# shiftreg-io.net
KiCad netlist of a schematic drawn in EAGLE
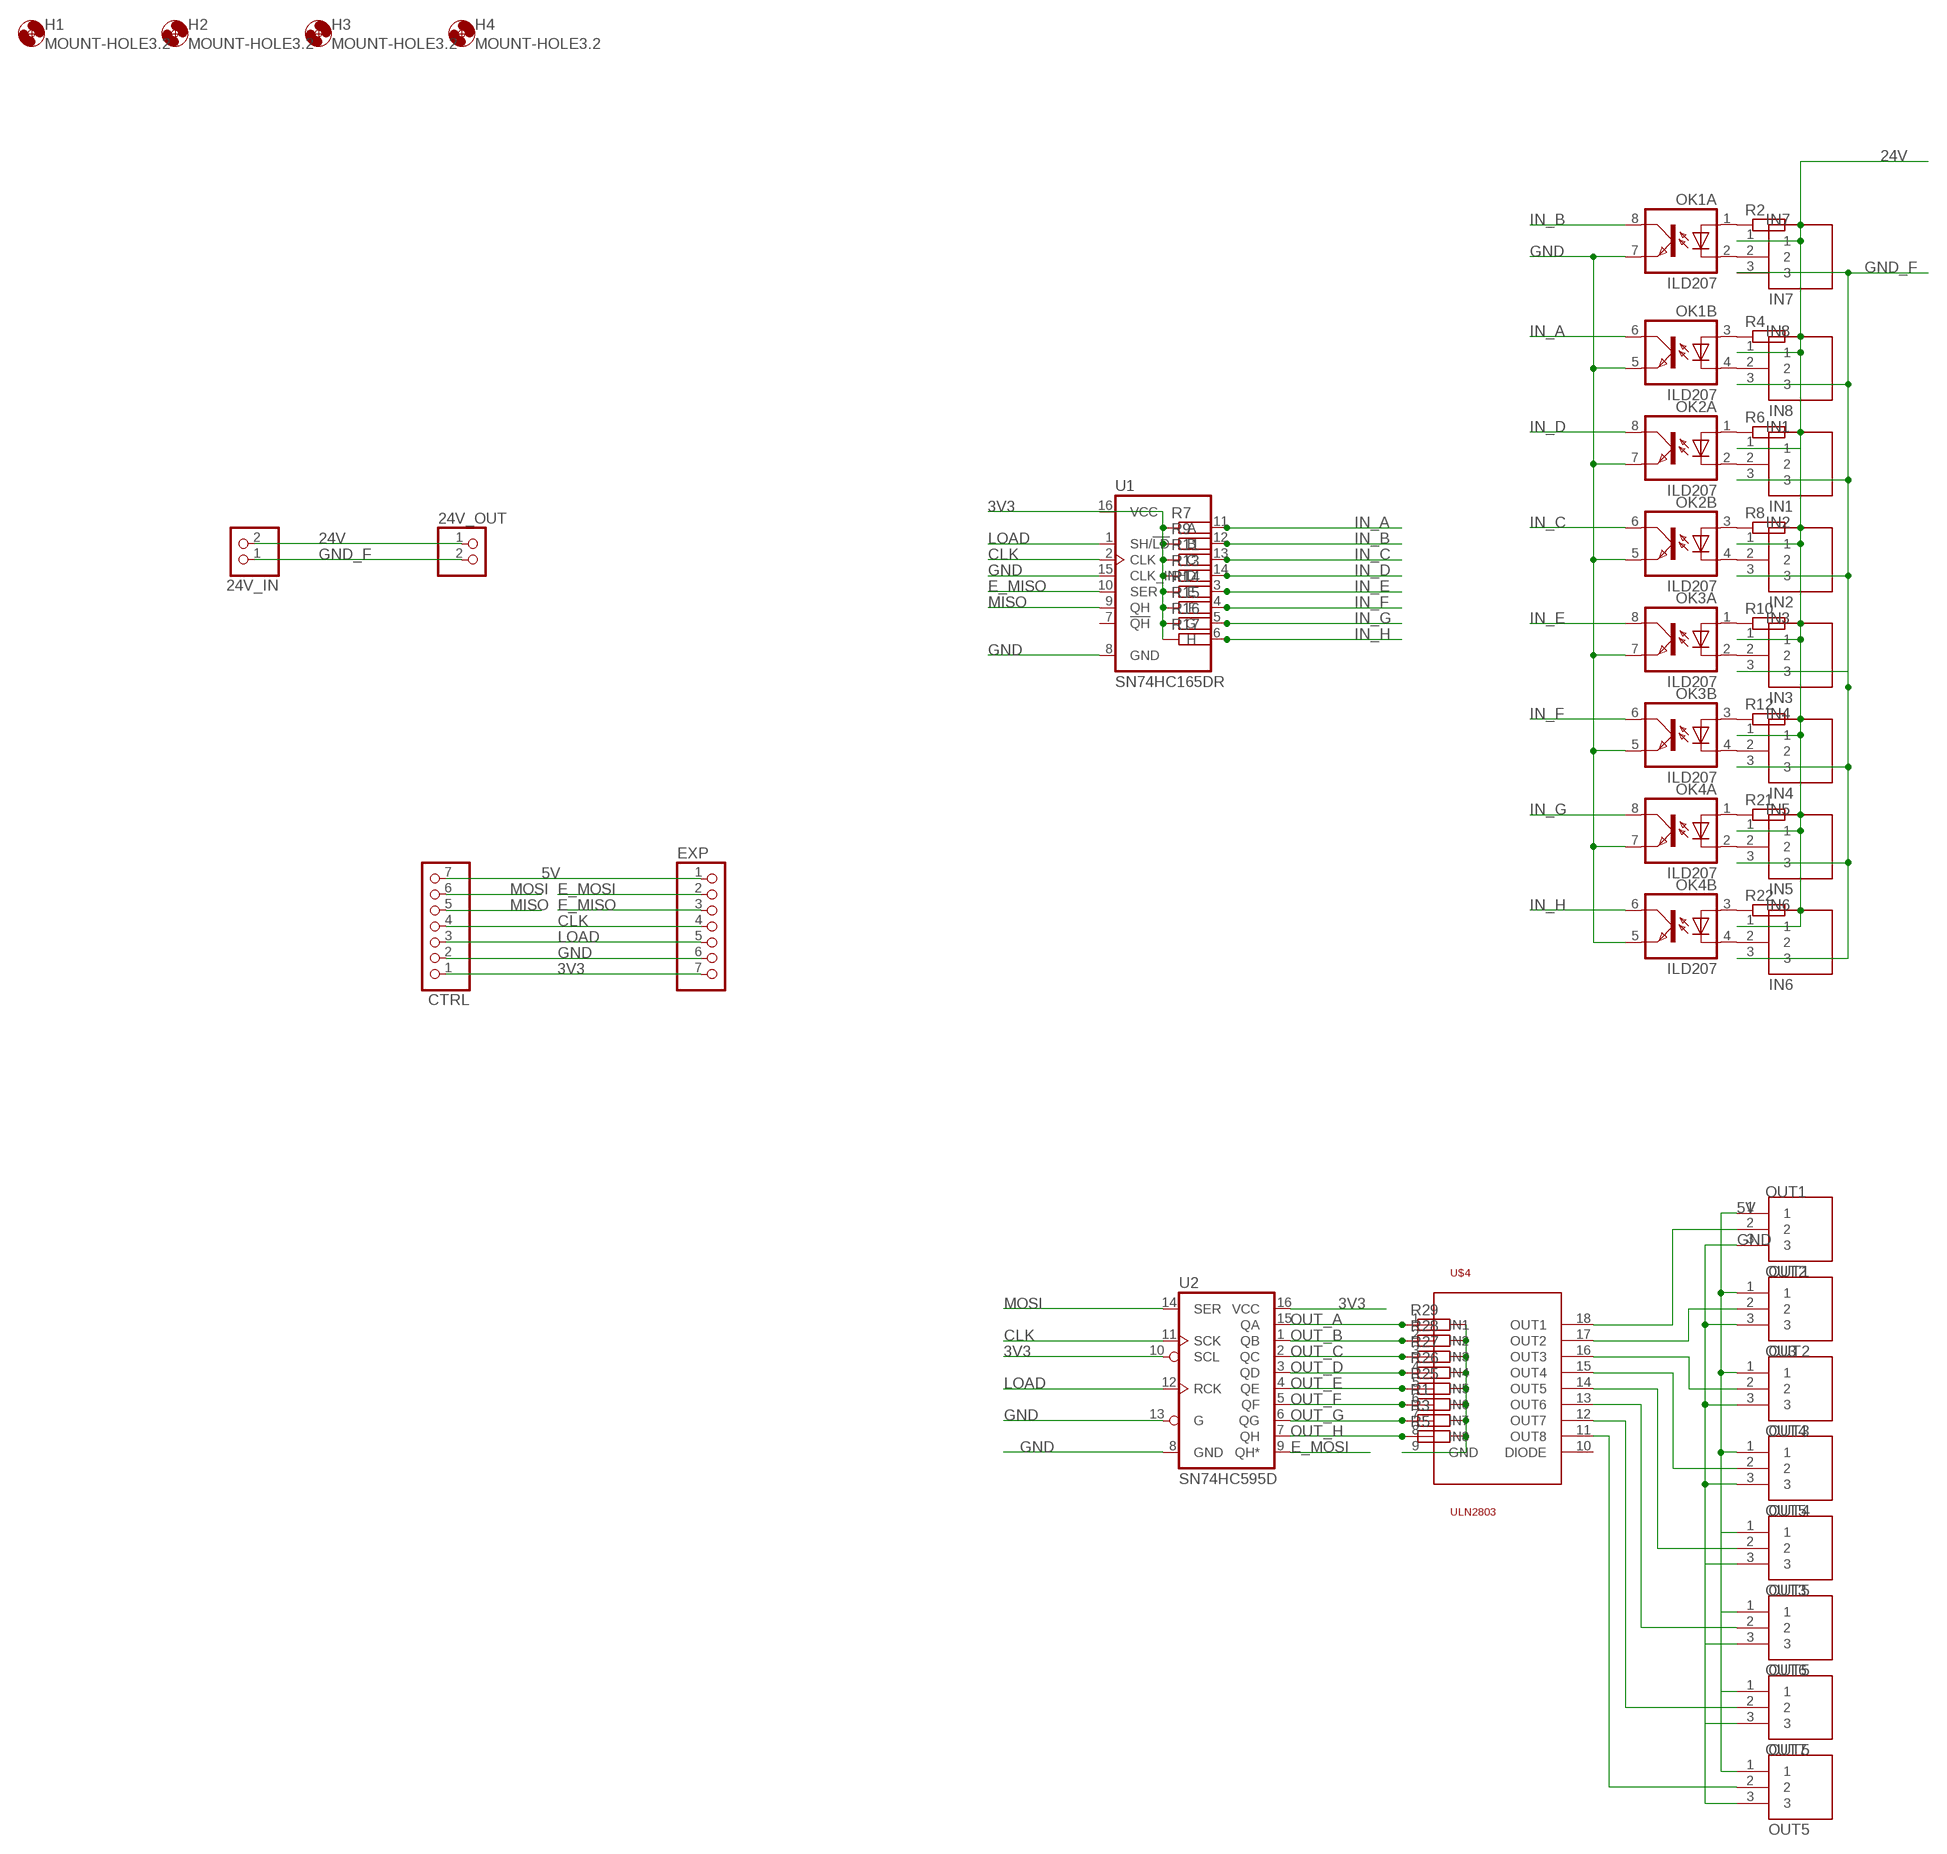
[diagram p0: schematic, sheet 1]

(export (version "E")
  (design (tool "Eeschema 10.0.6"))
  (components
    (comp (ref "24V_IN")
      (value "PINHD-1X2")
      (footprint "eagle-import:1X02")
      (libsource (lib "eagle-import") (part "PINHD-1X2"))
    )
    (comp (ref "24V_OUT")
      (value "PINHD-1X2")
      (footprint "eagle-import:1X02")
      (libsource (lib "eagle-import") (part "PINHD-1X2"))
    )
    (comp (ref "CTRL")
      (value "PINHD-1X7")
      (footprint "eagle-import:1X07")
      (libsource (lib "eagle-import") (part "PINHD-1X7"))
    )
    (comp (ref "EXP")
      (value "PINHD-1X7")
      (footprint "eagle-import:1X07")
      (libsource (lib "eagle-import") (part "PINHD-1X7"))
    )
    (comp (ref "H1")
      (value "MOUNT-HOLE3.2")
      (footprint "eagle-import:3,2")
      (libsource (lib "eagle-import") (part "MOUNT-HOLE3.2"))
    )
    (comp (ref "H2")
      (value "MOUNT-HOLE3.2")
      (footprint "eagle-import:3,2")
      (libsource (lib "eagle-import") (part "MOUNT-HOLE3.2"))
    )
    (comp (ref "H3")
      (value "MOUNT-HOLE3.2")
      (footprint "eagle-import:3,2")
      (libsource (lib "eagle-import") (part "MOUNT-HOLE3.2"))
    )
    (comp (ref "H4")
      (value "MOUNT-HOLE3.2")
      (footprint "eagle-import:3,2")
      (libsource (lib "eagle-import") (part "MOUNT-HOLE3.2"))
    )
    (comp (ref "IN1")
      (value "IN1")
      (footprint "eagle-import:TE_284512-3")
      (fields (field (name "COMMENT") "284512-3") (field (name "MF") "TE Connectivity"))
      (libsource (lib "eagle-import") (part "284512-3"))
    )
    (comp (ref "IN2")
      (value "IN2")
      (footprint "eagle-import:TE_284512-3")
      (fields (field (name "COMMENT") "284512-3") (field (name "MF") "TE Connectivity"))
      (libsource (lib "eagle-import") (part "284512-3"))
    )
    (comp (ref "IN3")
      (value "IN3")
      (footprint "eagle-import:TE_284512-3")
      (fields (field (name "COMMENT") "284512-3") (field (name "MF") "TE Connectivity"))
      (libsource (lib "eagle-import") (part "284512-3"))
    )
    (comp (ref "IN4")
      (value "IN4")
      (footprint "eagle-import:TE_284512-3")
      (fields (field (name "COMMENT") "284512-3") (field (name "MF") "TE Connectivity"))
      (libsource (lib "eagle-import") (part "284512-3"))
    )
    (comp (ref "IN5")
      (value "IN5")
      (footprint "eagle-import:TE_284512-3")
      (fields (field (name "COMMENT") "284512-3") (field (name "MF") "TE Connectivity"))
      (libsource (lib "eagle-import") (part "284512-3"))
    )
    (comp (ref "IN6")
      (value "IN6")
      (footprint "eagle-import:TE_284512-3")
      (fields (field (name "COMMENT") "284512-3") (field (name "MF") "TE Connectivity"))
      (libsource (lib "eagle-import") (part "284512-3"))
    )
    (comp (ref "IN7")
      (value "IN7")
      (footprint "eagle-import:TE_284512-3")
      (fields (field (name "COMMENT") "284512-3") (field (name "MF") "TE Connectivity"))
      (libsource (lib "eagle-import") (part "284512-3"))
    )
    (comp (ref "IN8")
      (value "IN8")
      (footprint "eagle-import:TE_284512-3")
      (fields (field (name "COMMENT") "284512-3") (field (name "MF") "TE Connectivity"))
      (libsource (lib "eagle-import") (part "284512-3"))
    )
    (comp (ref "OK1")
      (value "ILD207")
      (footprint "eagle-import:SOIC08")
      (fields (field (name "MF") "VISHAY/TELEFUNKEN") (field (name "MPN") "ILD207T"))
      (libsource (lib "eagle-import") (part "ILD207"))
    )
    (comp (ref "OK2")
      (value "ILD207")
      (footprint "eagle-import:SOIC08")
      (fields (field (name "MF") "VISHAY/TELEFUNKEN") (field (name "MPN") "ILD207T"))
      (libsource (lib "eagle-import") (part "ILD207"))
    )
    (comp (ref "OK3")
      (value "ILD207")
      (footprint "eagle-import:SOIC08")
      (fields (field (name "MF") "VISHAY/TELEFUNKEN") (field (name "MPN") "ILD207T"))
      (libsource (lib "eagle-import") (part "ILD207"))
    )
    (comp (ref "OK4")
      (value "ILD207")
      (footprint "eagle-import:SOIC08")
      (fields (field (name "MF") "VISHAY/TELEFUNKEN") (field (name "MPN") "ILD207T"))
      (libsource (lib "eagle-import") (part "ILD207"))
    )
    (comp (ref "OU3")
      (value "OUT3")
      (footprint "eagle-import:TE_284512-3")
      (fields (field (name "COMMENT") "284512-3") (field (name "MF") "TE Connectivity"))
      (libsource (lib "eagle-import") (part "284512-3"))
    )
    (comp (ref "OUT1")
      (value "OUT1")
      (footprint "eagle-import:TE_284512-3")
      (fields (field (name "COMMENT") "284512-3") (field (name "MF") "TE Connectivity"))
      (libsource (lib "eagle-import") (part "284512-3"))
    )
    (comp (ref "OUT2")
      (value "OUT2")
      (footprint "eagle-import:TE_284512-3")
      (fields (field (name "COMMENT") "284512-3") (field (name "MF") "TE Connectivity"))
      (libsource (lib "eagle-import") (part "284512-3"))
    )
    (comp (ref "OUT3")
      (value "OUT5")
      (footprint "eagle-import:TE_284512-3")
      (fields (field (name "COMMENT") "284512-3") (field (name "MF") "TE Connectivity"))
      (libsource (lib "eagle-import") (part "284512-3"))
    )
    (comp (ref "OUT4")
      (value "OUT4")
      (footprint "eagle-import:TE_284512-3")
      (fields (field (name "COMMENT") "284512-3") (field (name "MF") "TE Connectivity"))
      (libsource (lib "eagle-import") (part "284512-3"))
    )
    (comp (ref "OUT5")
      (value "OUT5")
      (footprint "eagle-import:TE_284512-3")
      (fields (field (name "COMMENT") "284512-3") (field (name "MF") "TE Connectivity"))
      (libsource (lib "eagle-import") (part "284512-3"))
    )
    (comp (ref "OUT6")
      (value "OUT5")
      (footprint "eagle-import:TE_284512-3")
      (fields (field (name "COMMENT") "284512-3") (field (name "MF") "TE Connectivity"))
      (libsource (lib "eagle-import") (part "284512-3"))
    )
    (comp (ref "OUT7")
      (value "OUT5")
      (footprint "eagle-import:TE_284512-3")
      (fields (field (name "COMMENT") "284512-3") (field (name "MF") "TE Connectivity"))
      (libsource (lib "eagle-import") (part "284512-3"))
    )
    (comp (ref "R1")
      (value "R-EU_M0805")
      (footprint "eagle-import:M0805")
      (libsource (lib "eagle-import") (part "R-EU_M0805"))
    )
    (comp (ref "R2")
      (value "R-EU_M0805")
      (footprint "eagle-import:M0805")
      (libsource (lib "eagle-import") (part "R-EU_M0805"))
    )
    (comp (ref "R3")
      (value "R-EU_M0805")
      (footprint "eagle-import:M0805")
      (libsource (lib "eagle-import") (part "R-EU_M0805"))
    )
    (comp (ref "R4")
      (value "R-EU_M0805")
      (footprint "eagle-import:M0805")
      (libsource (lib "eagle-import") (part "R-EU_M0805"))
    )
    (comp (ref "R5")
      (value "R-EU_M0805")
      (footprint "eagle-import:M0805")
      (libsource (lib "eagle-import") (part "R-EU_M0805"))
    )
    (comp (ref "R6")
      (value "R-EU_M0805")
      (footprint "eagle-import:M0805")
      (libsource (lib "eagle-import") (part "R-EU_M0805"))
    )
    (comp (ref "R7")
      (value "R-EU_M0805")
      (footprint "eagle-import:M0805")
      (libsource (lib "eagle-import") (part "R-EU_M0805"))
    )
    (comp (ref "R8")
      (value "R-EU_M0805")
      (footprint "eagle-import:M0805")
      (libsource (lib "eagle-import") (part "R-EU_M0805"))
    )
    (comp (ref "R9")
      (value "R-EU_M0805")
      (footprint "eagle-import:M0805")
      (libsource (lib "eagle-import") (part "R-EU_M0805"))
    )
    (comp (ref "R10")
      (value "R-EU_M0805")
      (footprint "eagle-import:M0805")
      (libsource (lib "eagle-import") (part "R-EU_M0805"))
    )
    (comp (ref "R11")
      (value "R-EU_M0805")
      (footprint "eagle-import:M0805")
      (libsource (lib "eagle-import") (part "R-EU_M0805"))
    )
    (comp (ref "R12")
      (value "R-EU_M0805")
      (footprint "eagle-import:M0805")
      (libsource (lib "eagle-import") (part "R-EU_M0805"))
    )
    (comp (ref "R13")
      (value "R-EU_M0805")
      (footprint "eagle-import:M0805")
      (libsource (lib "eagle-import") (part "R-EU_M0805"))
    )
    (comp (ref "R14")
      (value "R-EU_M0805")
      (footprint "eagle-import:M0805")
      (libsource (lib "eagle-import") (part "R-EU_M0805"))
    )
    (comp (ref "R15")
      (value "R-EU_M0805")
      (footprint "eagle-import:M0805")
      (libsource (lib "eagle-import") (part "R-EU_M0805"))
    )
    (comp (ref "R16")
      (value "R-EU_M0805")
      (footprint "eagle-import:M0805")
      (libsource (lib "eagle-import") (part "R-EU_M0805"))
    )
    (comp (ref "R17")
      (value "R-EU_M0805")
      (footprint "eagle-import:M0805")
      (libsource (lib "eagle-import") (part "R-EU_M0805"))
    )
    (comp (ref "R21")
      (value "R-EU_M0805")
      (footprint "eagle-import:M0805")
      (libsource (lib "eagle-import") (part "R-EU_M0805"))
    )
    (comp (ref "R22")
      (value "R-EU_M0805")
      (footprint "eagle-import:M0805")
      (libsource (lib "eagle-import") (part "R-EU_M0805"))
    )
    (comp (ref "R25")
      (value "R-EU_M0805")
      (footprint "eagle-import:M0805")
      (libsource (lib "eagle-import") (part "R-EU_M0805"))
    )
    (comp (ref "R26")
      (value "R-EU_M0805")
      (footprint "eagle-import:M0805")
      (libsource (lib "eagle-import") (part "R-EU_M0805"))
    )
    (comp (ref "R27")
      (value "R-EU_M0805")
      (footprint "eagle-import:M0805")
      (libsource (lib "eagle-import") (part "R-EU_M0805"))
    )
    (comp (ref "R28")
      (value "R-EU_M0805")
      (footprint "eagle-import:M0805")
      (libsource (lib "eagle-import") (part "R-EU_M0805"))
    )
    (comp (ref "R29")
      (value "R-EU_M0805")
      (footprint "eagle-import:M0805")
      (libsource (lib "eagle-import") (part "R-EU_M0805"))
    )
    (comp (ref "U$4")
      (value "ULN2803")
      (footprint "eagle-import:SO18L")
      (libsource (lib "eagle-import") (part "ULN2803"))
    )
    (comp (ref "U1")
      (value "SN74HC165DR")
      (footprint "eagle-import:SO16")
      (libsource (lib "eagle-import") (part "74165DHC"))
    )
    (comp (ref "U2")
      (value "SN74HC595D")
      (footprint "eagle-import:SO16")
      (libsource (lib "eagle-import") (part "74595DHC"))
    )
  )
  (nets
    (net (code "1") (name "/3V3") (class "Default")
      (node (ref "CTRL") (pin "1") (pinfunction "1_1") (pintype "passive"))
      (node (ref "EXP") (pin "7") (pinfunction "7_7") (pintype "passive"))
      (node (ref "R11") (pin "1") (pinfunction "1_1") (pintype "passive"))
      (node (ref "R13") (pin "1") (pinfunction "1_1") (pintype "passive"))
      (node (ref "R14") (pin "1") (pinfunction "1_1") (pintype "passive"))
      (node (ref "R15") (pin "1") (pinfunction "1_1") (pintype "passive"))
      (node (ref "R16") (pin "1") (pinfunction "1_1") (pintype "passive"))
      (node (ref "R17") (pin "1") (pinfunction "1_1") (pintype "passive"))
      (node (ref "R7") (pin "1") (pinfunction "1_1") (pintype "passive"))
      (node (ref "R9") (pin "1") (pinfunction "1_1") (pintype "passive"))
      (node (ref "U1") (pin "16") (pinfunction "VCC_16") (pintype "power_in"))
      (node (ref "U2") (pin "10") (pinfunction "SCL_10") (pintype "input"))
      (node (ref "U2") (pin "16") (pinfunction "VCC_16") (pintype "power_in"))
    )
    (net (code "2") (name "/5V") (class "Default")
      (node (ref "CTRL") (pin "7") (pinfunction "7_7") (pintype "passive"))
      (node (ref "EXP") (pin "1") (pinfunction "1_1") (pintype "passive"))
      (node (ref "OU3") (pin "1") (pinfunction "1_1") (pintype "passive"))
      (node (ref "OUT1") (pin "1") (pinfunction "1_1") (pintype "passive"))
      (node (ref "OUT2") (pin "1") (pinfunction "1_1") (pintype "passive"))
      (node (ref "OUT3") (pin "1") (pinfunction "1_1") (pintype "passive"))
      (node (ref "OUT4") (pin "1") (pinfunction "1_1") (pintype "passive"))
      (node (ref "OUT5") (pin "1") (pinfunction "1_1") (pintype "passive"))
      (node (ref "OUT6") (pin "1") (pinfunction "1_1") (pintype "passive"))
      (node (ref "OUT7") (pin "1") (pinfunction "1_1") (pintype "passive"))
    )
    (net (code "3") (name "/24V") (class "Default")
      (node (ref "24V_IN") (pin "2") (pinfunction "2_2") (pintype "passive"))
      (node (ref "24V_OUT") (pin "1") (pinfunction "1_1") (pintype "passive"))
      (node (ref "IN1") (pin "1") (pinfunction "1_1") (pintype "passive"))
      (node (ref "IN2") (pin "1") (pinfunction "1_1") (pintype "passive"))
      (node (ref "IN3") (pin "1") (pinfunction "1_1") (pintype "passive"))
      (node (ref "IN4") (pin "1") (pinfunction "1_1") (pintype "passive"))
      (node (ref "IN5") (pin "1") (pinfunction "1_1") (pintype "passive"))
      (node (ref "IN6") (pin "1") (pinfunction "1_1") (pintype "passive"))
      (node (ref "IN7") (pin "1") (pinfunction "1_1") (pintype "passive"))
      (node (ref "IN8") (pin "1") (pinfunction "1_1") (pintype "passive"))
      (node (ref "R10") (pin "2") (pinfunction "2_2") (pintype "passive"))
      (node (ref "R12") (pin "2") (pinfunction "2_2") (pintype "passive"))
      (node (ref "R2") (pin "2") (pinfunction "2_2") (pintype "passive"))
      (node (ref "R21") (pin "2") (pinfunction "2_2") (pintype "passive"))
      (node (ref "R22") (pin "2") (pinfunction "2_2") (pintype "passive"))
      (node (ref "R4") (pin "2") (pinfunction "2_2") (pintype "passive"))
      (node (ref "R6") (pin "2") (pinfunction "2_2") (pintype "passive"))
      (node (ref "R8") (pin "2") (pinfunction "2_2") (pintype "passive"))
    )
    (net (code "4") (name "/CLK") (class "Default")
      (node (ref "CTRL") (pin "4") (pinfunction "4_4") (pintype "passive"))
      (node (ref "EXP") (pin "4") (pinfunction "4_4") (pintype "passive"))
      (node (ref "U1") (pin "2") (pinfunction "CLK_2") (pintype "input"))
      (node (ref "U2") (pin "11") (pinfunction "SCK_11") (pintype "input"))
    )
    (net (code "5") (name "/DIODE") (class "Default")
      (node (ref "U$4") (pin "10") (pinfunction "DIODE_10") (pintype "power_in"))
    )
    (net (code "6") (name "/E_MISO") (class "Default")
      (node (ref "EXP") (pin "3") (pinfunction "3_3") (pintype "passive"))
      (node (ref "U1") (pin "10") (pinfunction "SER_10") (pintype "input"))
    )
    (net (code "7") (name "/E_MOSI") (class "Default")
      (node (ref "EXP") (pin "2") (pinfunction "2_2") (pintype "passive"))
      (node (ref "U2") (pin "9") (pinfunction "QH*_9") (pintype "tri_state"))
    )
    (net (code "8") (name "/GND") (class "Default")
      (node (ref "CTRL") (pin "2") (pinfunction "2_2") (pintype "passive"))
      (node (ref "EXP") (pin "6") (pinfunction "6_6") (pintype "passive"))
      (node (ref "OK1") (pin "5") (pinfunction "EMIT_5") (pintype "passive"))
      (node (ref "OK1") (pin "7") (pinfunction "EMIT_7") (pintype "passive"))
      (node (ref "OK2") (pin "5") (pinfunction "EMIT_5") (pintype "passive"))
      (node (ref "OK2") (pin "7") (pinfunction "EMIT_7") (pintype "passive"))
      (node (ref "OK3") (pin "5") (pinfunction "EMIT_5") (pintype "passive"))
      (node (ref "OK3") (pin "7") (pinfunction "EMIT_7") (pintype "passive"))
      (node (ref "OK4") (pin "5") (pinfunction "EMIT_5") (pintype "passive"))
      (node (ref "OK4") (pin "7") (pinfunction "EMIT_7") (pintype "passive"))
      (node (ref "OU3") (pin "3") (pinfunction "3_3") (pintype "passive"))
      (node (ref "OUT1") (pin "3") (pinfunction "3_3") (pintype "passive"))
      (node (ref "OUT2") (pin "3") (pinfunction "3_3") (pintype "passive"))
      (node (ref "OUT3") (pin "3") (pinfunction "3_3") (pintype "passive"))
      (node (ref "OUT4") (pin "3") (pinfunction "3_3") (pintype "passive"))
      (node (ref "OUT5") (pin "3") (pinfunction "3_3") (pintype "passive"))
      (node (ref "OUT6") (pin "3") (pinfunction "3_3") (pintype "passive"))
      (node (ref "OUT7") (pin "3") (pinfunction "3_3") (pintype "passive"))
      (node (ref "R1") (pin "2") (pinfunction "2_2") (pintype "passive"))
      (node (ref "R25") (pin "2") (pinfunction "2_2") (pintype "passive"))
      (node (ref "R26") (pin "2") (pinfunction "2_2") (pintype "passive"))
      (node (ref "R27") (pin "2") (pinfunction "2_2") (pintype "passive"))
      (node (ref "R28") (pin "2") (pinfunction "2_2") (pintype "passive"))
      (node (ref "R29") (pin "2") (pinfunction "2_2") (pintype "passive"))
      (node (ref "R3") (pin "2") (pinfunction "2_2") (pintype "passive"))
      (node (ref "R5") (pin "2") (pinfunction "2_2") (pintype "passive"))
      (node (ref "U$4") (pin "9") (pinfunction "GND_9") (pintype "power_in"))
      (node (ref "U1") (pin "15") (pinfunction "CLK_INH_15") (pintype "input"))
      (node (ref "U1") (pin "8") (pinfunction "GND_8") (pintype "power_in"))
      (node (ref "U2") (pin "13") (pinfunction "G_13") (pintype "input"))
      (node (ref "U2") (pin "8") (pinfunction "GND_8") (pintype "power_in"))
    )
    (net (code "9") (name "/GND_F") (class "Default")
      (node (ref "24V_IN") (pin "1") (pinfunction "1_1") (pintype "passive"))
      (node (ref "24V_OUT") (pin "2") (pinfunction "2_2") (pintype "passive"))
      (node (ref "IN1") (pin "3") (pinfunction "3_3") (pintype "passive"))
      (node (ref "IN2") (pin "3") (pinfunction "3_3") (pintype "passive"))
      (node (ref "IN3") (pin "3") (pinfunction "3_3") (pintype "passive"))
      (node (ref "IN4") (pin "3") (pinfunction "3_3") (pintype "passive"))
      (node (ref "IN5") (pin "3") (pinfunction "3_3") (pintype "passive"))
      (node (ref "IN6") (pin "3") (pinfunction "3_3") (pintype "passive"))
      (node (ref "IN7") (pin "3") (pinfunction "3_3") (pintype "passive"))
      (node (ref "IN8") (pin "3") (pinfunction "3_3") (pintype "passive"))
    )
    (net (code "10") (name "/IN_A") (class "Default")
      (node (ref "OK1") (pin "6") (pinfunction "COL_6") (pintype "passive"))
      (node (ref "R7") (pin "2") (pinfunction "2_2") (pintype "passive"))
      (node (ref "U1") (pin "11") (pinfunction "A_11") (pintype "tri_state"))
    )
    (net (code "11") (name "/IN_B") (class "Default")
      (node (ref "OK1") (pin "8") (pinfunction "COL_8") (pintype "passive"))
      (node (ref "R9") (pin "2") (pinfunction "2_2") (pintype "passive"))
      (node (ref "U1") (pin "12") (pinfunction "B_12") (pintype "tri_state"))
    )
    (net (code "12") (name "/IN_C") (class "Default")
      (node (ref "OK2") (pin "6") (pinfunction "COL_6") (pintype "passive"))
      (node (ref "R11") (pin "2") (pinfunction "2_2") (pintype "passive"))
      (node (ref "U1") (pin "13") (pinfunction "C_13") (pintype "tri_state"))
    )
    (net (code "13") (name "/IN_D") (class "Default")
      (node (ref "OK2") (pin "8") (pinfunction "COL_8") (pintype "passive"))
      (node (ref "R13") (pin "2") (pinfunction "2_2") (pintype "passive"))
      (node (ref "U1") (pin "14") (pinfunction "D_14") (pintype "tri_state"))
    )
    (net (code "14") (name "/IN_E") (class "Default")
      (node (ref "OK3") (pin "8") (pinfunction "COL_8") (pintype "passive"))
      (node (ref "R14") (pin "2") (pinfunction "2_2") (pintype "passive"))
      (node (ref "U1") (pin "3") (pinfunction "E_3") (pintype "tri_state"))
    )
    (net (code "15") (name "/IN_F") (class "Default")
      (node (ref "OK3") (pin "6") (pinfunction "COL_6") (pintype "passive"))
      (node (ref "R15") (pin "2") (pinfunction "2_2") (pintype "passive"))
      (node (ref "U1") (pin "4") (pinfunction "F_4") (pintype "tri_state"))
    )
    (net (code "16") (name "/IN_G") (class "Default")
      (node (ref "OK4") (pin "8") (pinfunction "COL_8") (pintype "passive"))
      (node (ref "R16") (pin "2") (pinfunction "2_2") (pintype "passive"))
      (node (ref "U1") (pin "5") (pinfunction "G_5") (pintype "tri_state"))
    )
    (net (code "17") (name "/IN_H") (class "Default")
      (node (ref "OK4") (pin "6") (pinfunction "COL_6") (pintype "passive"))
      (node (ref "R17") (pin "2") (pinfunction "2_2") (pintype "passive"))
      (node (ref "U1") (pin "6") (pinfunction "H_6") (pintype "tri_state"))
    )
    (net (code "18") (name "/LOAD") (class "Default")
      (node (ref "CTRL") (pin "3") (pinfunction "3_3") (pintype "passive"))
      (node (ref "EXP") (pin "5") (pinfunction "5_5") (pintype "passive"))
      (node (ref "U1") (pin "1") (pinfunction "SH/~{LD}_1") (pintype "input"))
      (node (ref "U2") (pin "12") (pinfunction "RCK_12") (pintype "input"))
    )
    (net (code "19") (name "/MISO") (class "Default")
      (node (ref "CTRL") (pin "5") (pinfunction "5_5") (pintype "passive"))
      (node (ref "U1") (pin "9") (pinfunction "QH_9") (pintype "tri_state"))
    )
    (net (code "20") (name "/MOSI") (class "Default")
      (node (ref "CTRL") (pin "6") (pinfunction "6_6") (pintype "passive"))
      (node (ref "U2") (pin "14") (pinfunction "SER_14") (pintype "input"))
    )
    (net (code "21") (name "/OUT_A") (class "Default")
      (node (ref "R29") (pin "1") (pinfunction "1_1") (pintype "passive"))
      (node (ref "U$4") (pin "1") (pinfunction "IN1_1") (pintype "input"))
      (node (ref "U2") (pin "15") (pinfunction "QA_15") (pintype "tri_state"))
    )
    (net (code "22") (name "/OUT_B") (class "Default")
      (node (ref "R28") (pin "1") (pinfunction "1_1") (pintype "passive"))
      (node (ref "U$4") (pin "2") (pinfunction "IN2_2") (pintype "input"))
      (node (ref "U2") (pin "1") (pinfunction "QB_1") (pintype "tri_state"))
    )
    (net (code "23") (name "/OUT_C") (class "Default")
      (node (ref "R27") (pin "1") (pinfunction "1_1") (pintype "passive"))
      (node (ref "U$4") (pin "3") (pinfunction "IN3_3") (pintype "input"))
      (node (ref "U2") (pin "2") (pinfunction "QC_2") (pintype "tri_state"))
    )
    (net (code "24") (name "/OUT_D") (class "Default")
      (node (ref "R26") (pin "1") (pinfunction "1_1") (pintype "passive"))
      (node (ref "U$4") (pin "4") (pinfunction "IN4_4") (pintype "input"))
      (node (ref "U2") (pin "3") (pinfunction "QD_3") (pintype "tri_state"))
    )
    (net (code "25") (name "/OUT_E") (class "Default")
      (node (ref "R25") (pin "1") (pinfunction "1_1") (pintype "passive"))
      (node (ref "U$4") (pin "5") (pinfunction "IN5_5") (pintype "input"))
      (node (ref "U2") (pin "4") (pinfunction "QE_4") (pintype "tri_state"))
    )
    (net (code "26") (name "/OUT_F") (class "Default")
      (node (ref "R1") (pin "1") (pinfunction "1_1") (pintype "passive"))
      (node (ref "U$4") (pin "6") (pinfunction "IN6_6") (pintype "input"))
      (node (ref "U2") (pin "5") (pinfunction "QF_5") (pintype "tri_state"))
    )
    (net (code "27") (name "/OUT_G") (class "Default")
      (node (ref "R3") (pin "1") (pinfunction "1_1") (pintype "passive"))
      (node (ref "U$4") (pin "7") (pinfunction "IN7_7") (pintype "input"))
      (node (ref "U2") (pin "6") (pinfunction "QG_6") (pintype "tri_state"))
    )
    (net (code "28") (name "/OUT_H") (class "Default")
      (node (ref "R5") (pin "1") (pinfunction "1_1") (pintype "passive"))
      (node (ref "U$4") (pin "8") (pinfunction "IN8_8") (pintype "input"))
      (node (ref "U2") (pin "7") (pinfunction "QH_7") (pintype "tri_state"))
    )
    (net (code "29") (name "Net-(OK1A-A)") (class "Default")
      (node (ref "OK1") (pin "1") (pinfunction "A_1") (pintype "passive"))
      (node (ref "R2") (pin "1") (pinfunction "1_1") (pintype "passive"))
    )
    (net (code "30") (name "Net-(OK1A-C)") (class "Default")
      (node (ref "IN7") (pin "2") (pinfunction "2_2") (pintype "passive"))
      (node (ref "OK1") (pin "2") (pinfunction "C_2") (pintype "passive"))
    )
    (net (code "31") (name "Net-(OK1B-A)") (class "Default")
      (node (ref "OK1") (pin "3") (pinfunction "A_3") (pintype "passive"))
      (node (ref "R4") (pin "1") (pinfunction "1_1") (pintype "passive"))
    )
    (net (code "32") (name "Net-(OK1B-C)") (class "Default")
      (node (ref "IN8") (pin "2") (pinfunction "2_2") (pintype "passive"))
      (node (ref "OK1") (pin "4") (pinfunction "C_4") (pintype "passive"))
    )
    (net (code "33") (name "Net-(OK2A-A)") (class "Default")
      (node (ref "OK2") (pin "1") (pinfunction "A_1") (pintype "passive"))
      (node (ref "R6") (pin "1") (pinfunction "1_1") (pintype "passive"))
    )
    (net (code "34") (name "Net-(OK2A-C)") (class "Default")
      (node (ref "IN1") (pin "2") (pinfunction "2_2") (pintype "passive"))
      (node (ref "OK2") (pin "2") (pinfunction "C_2") (pintype "passive"))
    )
    (net (code "35") (name "Net-(OK2B-A)") (class "Default")
      (node (ref "OK2") (pin "3") (pinfunction "A_3") (pintype "passive"))
      (node (ref "R8") (pin "1") (pinfunction "1_1") (pintype "passive"))
    )
    (net (code "36") (name "Net-(OK2B-C)") (class "Default")
      (node (ref "IN2") (pin "2") (pinfunction "2_2") (pintype "passive"))
      (node (ref "OK2") (pin "4") (pinfunction "C_4") (pintype "passive"))
    )
    (net (code "37") (name "Net-(OK3A-A)") (class "Default")
      (node (ref "OK3") (pin "1") (pinfunction "A_1") (pintype "passive"))
      (node (ref "R10") (pin "1") (pinfunction "1_1") (pintype "passive"))
    )
    (net (code "38") (name "Net-(OK3A-C)") (class "Default")
      (node (ref "IN3") (pin "2") (pinfunction "2_2") (pintype "passive"))
      (node (ref "OK3") (pin "2") (pinfunction "C_2") (pintype "passive"))
    )
    (net (code "39") (name "Net-(OK3B-A)") (class "Default")
      (node (ref "OK3") (pin "3") (pinfunction "A_3") (pintype "passive"))
      (node (ref "R12") (pin "1") (pinfunction "1_1") (pintype "passive"))
    )
    (net (code "40") (name "Net-(OK3B-C)") (class "Default")
      (node (ref "IN4") (pin "2") (pinfunction "2_2") (pintype "passive"))
      (node (ref "OK3") (pin "4") (pinfunction "C_4") (pintype "passive"))
    )
    (net (code "41") (name "Net-(OK4A-A)") (class "Default")
      (node (ref "OK4") (pin "1") (pinfunction "A_1") (pintype "passive"))
      (node (ref "R21") (pin "1") (pinfunction "1_1") (pintype "passive"))
    )
    (net (code "42") (name "Net-(OK4A-C)") (class "Default")
      (node (ref "IN5") (pin "2") (pinfunction "2_2") (pintype "passive"))
      (node (ref "OK4") (pin "2") (pinfunction "C_2") (pintype "passive"))
    )
    (net (code "43") (name "Net-(OK4B-A)") (class "Default")
      (node (ref "OK4") (pin "3") (pinfunction "A_3") (pintype "passive"))
      (node (ref "R22") (pin "1") (pinfunction "1_1") (pintype "passive"))
    )
    (net (code "44") (name "Net-(OK4B-C)") (class "Default")
      (node (ref "IN6") (pin "2") (pinfunction "2_2") (pintype "passive"))
      (node (ref "OK4") (pin "4") (pinfunction "C_4") (pintype "passive"))
    )
    (net (code "45") (name "Net-(U$4-OUT1)") (class "Default")
      (node (ref "OUT1") (pin "2") (pinfunction "2_2") (pintype "passive"))
      (node (ref "U$4") (pin "18") (pinfunction "OUT1_18") (pintype "open_collector"))
    )
    (net (code "46") (name "Net-(U$4-OUT2)") (class "Default")
      (node (ref "OUT2") (pin "2") (pinfunction "2_2") (pintype "passive"))
      (node (ref "U$4") (pin "17") (pinfunction "OUT2_17") (pintype "open_collector"))
    )
    (net (code "47") (name "Net-(U$4-OUT3)") (class "Default")
      (node (ref "OU3") (pin "2") (pinfunction "2_2") (pintype "passive"))
      (node (ref "U$4") (pin "16") (pinfunction "OUT3_16") (pintype "open_collector"))
    )
    (net (code "48") (name "Net-(U$4-OUT4)") (class "Default")
      (node (ref "OUT4") (pin "2") (pinfunction "2_2") (pintype "passive"))
      (node (ref "U$4") (pin "15") (pinfunction "OUT4_15") (pintype "open_collector"))
    )
    (net (code "49") (name "Net-(U$4-OUT5)") (class "Default")
      (node (ref "OUT5") (pin "2") (pinfunction "2_2") (pintype "passive"))
      (node (ref "U$4") (pin "14") (pinfunction "OUT5_14") (pintype "open_collector"))
    )
    (net (code "50") (name "Net-(U$4-OUT6)") (class "Default")
      (node (ref "OUT3") (pin "2") (pinfunction "2_2") (pintype "passive"))
      (node (ref "U$4") (pin "13") (pinfunction "OUT6_13") (pintype "open_collector"))
    )
    (net (code "51") (name "Net-(U$4-OUT7)") (class "Default")
      (node (ref "OUT6") (pin "2") (pinfunction "2_2") (pintype "passive"))
      (node (ref "U$4") (pin "12") (pinfunction "OUT7_12") (pintype "open_collector"))
    )
    (net (code "52") (name "Net-(U$4-OUT8)") (class "Default")
      (node (ref "OUT7") (pin "2") (pinfunction "2_2") (pintype "passive"))
      (node (ref "U$4") (pin "11") (pinfunction "OUT8_11") (pintype "open_collector"))
    )
    (net (code "53") (name "unconnected-(U1-~{QH}-Pad7)") (class "Default")
      (node (ref "U1") (pin "7") (pinfunction "~{QH}_7") (pintype "input"))
    )
  )
)
